# USB_HUB.net
KiCad netlist of a schematic drawn in Altium Designer
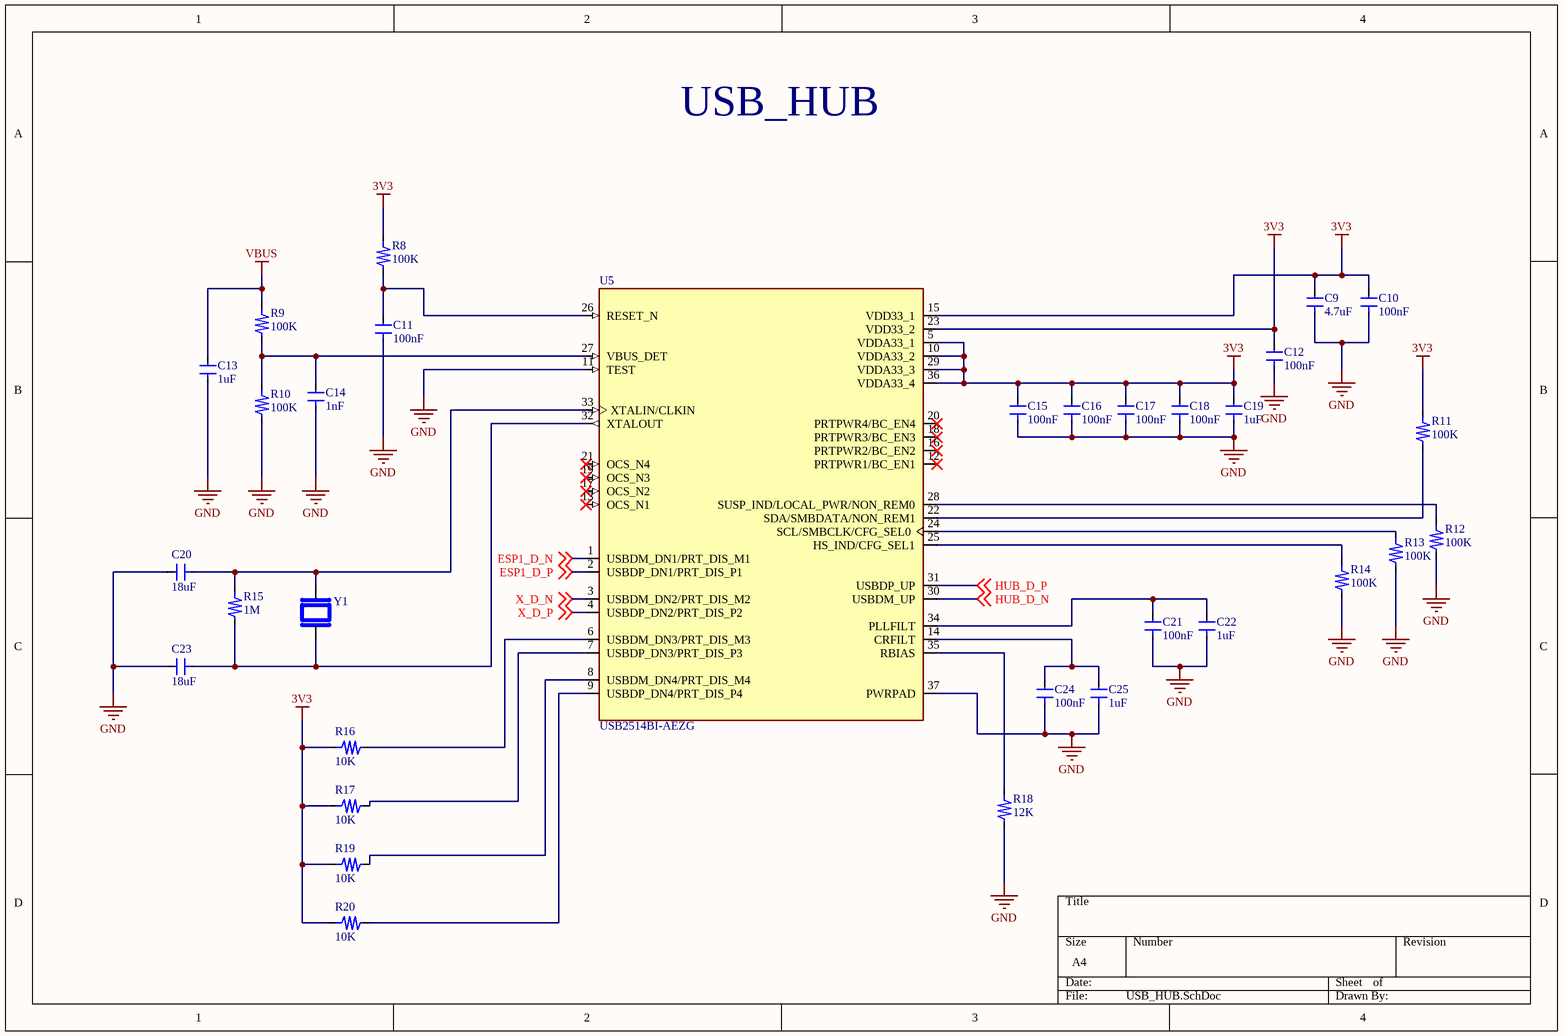
[diagram p0: USB_HUB.SchDoc]

(export (version "E")
  (design (tool "Eeschema 10.0.6"))
  (components
    (comp (ref "C9")
      (value "4.7uF")
      (footprint "CAP 0603")
      (fields (field (name "PART NUMBER") "CL10A475KL8NRNC"))
      (libsource (lib "Schlib2") (part "Capasitor"))
    )
    (comp (ref "C10")
      (value "100nF")
      (footprint "CAP 0603")
      (fields (field (name "PART NUMBER") "CC0603JRX7R9BB104"))
      (libsource (lib "Schlib2") (part "Capasitor"))
    )
    (comp (ref "C11")
      (value "100nF")
      (footprint "CAP 0603")
      (fields (field (name "PART NUMBER") "CC0603JRX7R9BB104"))
      (libsource (lib "Schlib2") (part "Capasitor"))
    )
    (comp (ref "C12")
      (value "100nF")
      (footprint "CAP 0603")
      (fields (field (name "PART NUMBER") "CC0603JRX7R9BB104"))
      (libsource (lib "Schlib2") (part "Capasitor"))
    )
    (comp (ref "C13")
      (value "1uF")
      (footprint "CAP 0603")
      (fields (field (name "PART NUMBER") "CC0603JRX7R7BB105"))
      (libsource (lib "Schlib2") (part "Capasitor"))
    )
    (comp (ref "C14")
      (value "1nF")
      (footprint "CAP 0603")
      (fields (field (name "PART NUMBER") "GRM1885C1H102JA01D"))
      (libsource (lib "Schlib2") (part "Capasitor"))
    )
    (comp (ref "C15")
      (value "100nF")
      (footprint "CAP 0603")
      (fields (field (name "PART NUMBER") "CC0603JRX7R9BB104"))
      (libsource (lib "Schlib2") (part "Capasitor"))
    )
    (comp (ref "C16")
      (value "100nF")
      (footprint "CAP 0603")
      (fields (field (name "PART NUMBER") "CC0603JRX7R9BB104"))
      (libsource (lib "Schlib2") (part "Capasitor"))
    )
    (comp (ref "C17")
      (value "100nF")
      (footprint "CAP 0603")
      (fields (field (name "PART NUMBER") "CC0603JRX7R9BB104"))
      (libsource (lib "Schlib2") (part "Capasitor"))
    )
    (comp (ref "C18")
      (value "100nF")
      (footprint "CAP 0603")
      (fields (field (name "PART NUMBER") "CC0603JRX7R9BB104"))
      (libsource (lib "Schlib2") (part "Capasitor"))
    )
    (comp (ref "C19")
      (value "1uF")
      (footprint "CAP 0603")
      (fields (field (name "PART NUMBER") "CC0603JRX7R7BB105"))
      (libsource (lib "Schlib2") (part "Capasitor"))
    )
    (comp (ref "C20")
      (value "18uF")
      (footprint "CAP 0603")
      (fields (field (name "PART NUMBER") "CC0603FRNPO9BN180"))
      (libsource (lib "Schlib2") (part "Capasitor"))
    )
    (comp (ref "C21")
      (value "100nF")
      (footprint "CAP 0603")
      (fields (field (name "PART NUMBER") "CC0603JRX7R9BB104"))
      (libsource (lib "Schlib2") (part "Capasitor"))
    )
    (comp (ref "C22")
      (value "1uF")
      (footprint "CAP 0603")
      (fields (field (name "PART NUMBER") "CC0603JRX7R7BB105"))
      (libsource (lib "Schlib2") (part "Capasitor"))
    )
    (comp (ref "C23")
      (value "18uF")
      (footprint "CAP 0603")
      (fields (field (name "PART NUMBER") "CC0603FRNPO9BN180"))
      (libsource (lib "Schlib2") (part "Capasitor"))
    )
    (comp (ref "C24")
      (value "100nF")
      (footprint "CAP 0603")
      (fields (field (name "PART NUMBER") "CC0603JRX7R9BB104"))
      (libsource (lib "Schlib2") (part "Capasitor"))
    )
    (comp (ref "C25")
      (value "1uF")
      (footprint "CAP 0603")
      (fields (field (name "PART NUMBER") "CC0603JRX7R7BB105"))
      (libsource (lib "Schlib2") (part "Capasitor"))
    )
    (comp (ref "R8")
      (value "100K")
      (footprint "RES 0603")
      (fields (field (name "PART NUMBER") "RS-03K104JT"))
      (libsource (lib "Schlib2") (part "Resistor"))
    )
    (comp (ref "R9")
      (value "100K")
      (footprint "RES 0603")
      (fields (field (name "PART NUMBER") "RS-03K104JT"))
      (libsource (lib "Schlib2") (part "Resistor"))
    )
    (comp (ref "R10")
      (value "100K")
      (footprint "RES 0603")
      (fields (field (name "PART NUMBER") "RS-03K104JT"))
      (libsource (lib "Schlib2") (part "Resistor"))
    )
    (comp (ref "R11")
      (value "100K")
      (footprint "RES 0603")
      (fields (field (name "PART NUMBER") "RS-03K104JT"))
      (libsource (lib "Schlib2") (part "Resistor"))
    )
    (comp (ref "R12")
      (value "100K")
      (footprint "RES 0603")
      (fields (field (name "PART NUMBER") "RS-03K104JT"))
      (libsource (lib "Schlib2") (part "Resistor"))
    )
    (comp (ref "R13")
      (value "100K")
      (footprint "RES 0603")
      (fields (field (name "PART NUMBER") "RS-03K104JT"))
      (libsource (lib "Schlib2") (part "Resistor"))
    )
    (comp (ref "R14")
      (value "100K")
      (footprint "RES 0603")
      (fields (field (name "PART NUMBER") "RS-03K104JT"))
      (libsource (lib "Schlib2") (part "Resistor"))
    )
    (comp (ref "R15")
      (value "1M")
      (footprint "RES 0603")
      (fields (field (name "PART NUMBER") "RS-03K1004FT"))
      (libsource (lib "Schlib2") (part "Resistor"))
    )
    (comp (ref "R16")
      (value "10K")
      (footprint "RES 0603")
      (fields (field (name "PART NUMBER") "RS-03K1002FT"))
      (libsource (lib "Schlib2") (part "Resistor"))
    )
    (comp (ref "R17")
      (value "10K")
      (footprint "RES 0603")
      (fields (field (name "PART NUMBER") "RS-03K1002FT"))
      (libsource (lib "Schlib2") (part "Resistor"))
    )
    (comp (ref "R18")
      (value "12K")
      (footprint "RES 0603")
      (fields (field (name "PART NUMBER") "RS-03K1202FT"))
      (libsource (lib "Schlib2") (part "Resistor"))
    )
    (comp (ref "R19")
      (value "10K")
      (footprint "RES 0603")
      (fields (field (name "PART NUMBER") "RS-03K1002FT"))
      (libsource (lib "Schlib2") (part "Resistor"))
    )
    (comp (ref "R20")
      (value "10K")
      (footprint "RES 0603")
      (fields (field (name "PART NUMBER") "RS-03K1002FT"))
      (libsource (lib "Schlib2") (part "Resistor"))
    )
    (comp (ref "U5")
      (value "USB2514BI-AEZG")
      (footprint "QFN50P600X600X100-37N")
      (description "USB Hub Controller USB 2.0 USB Interface 36-QFN (6x6)")
      (fields (field (name "PART NUMBER") "USB2514BI-AEZG-TR"))
      (libsource (lib "Schlib2") (part "USB2514BI-AEZG"))
    )
    (comp (ref "Y1")
      (value "ABLS-24.000MHZ-B4-T")
      (footprint "XTAL_ABLS-24.000MHZ-B4-T")
      (description "HC/49US (AT49) SMD LOW PROFILE CRYSTAL")
      (libsource (lib "Schlib2") (part "ABLS-24.000MHZ-B4-T"))
    )
  )
  (nets
    (net (code "1") (name "3V3") (class "Default")
      (node (ref "C10") (pin "2") (pinfunction "2_2") (pintype "passive"))
      (node (ref "C12") (pin "2") (pinfunction "2_2") (pintype "passive"))
      (node (ref "C15") (pin "2") (pinfunction "2_2") (pintype "passive"))
      (node (ref "C16") (pin "2") (pinfunction "2_2") (pintype "passive"))
      (node (ref "C17") (pin "2") (pinfunction "2_2") (pintype "passive"))
      (node (ref "C18") (pin "2") (pinfunction "2_2") (pintype "passive"))
      (node (ref "C19") (pin "2") (pinfunction "2_2") (pintype "passive"))
      (node (ref "C9") (pin "2") (pinfunction "2_2") (pintype "passive"))
      (node (ref "R11") (pin "1") (pinfunction "1_1") (pintype "passive"))
      (node (ref "R16") (pin "1") (pinfunction "1_1") (pintype "passive"))
      (node (ref "R17") (pin "1") (pinfunction "1_1") (pintype "passive"))
      (node (ref "R19") (pin "1") (pinfunction "1_1") (pintype "passive"))
      (node (ref "R20") (pin "1") (pinfunction "1_1") (pintype "passive"))
      (node (ref "R8") (pin "1") (pinfunction "1_1") (pintype "passive"))
      (node (ref "U5") (pin "10") (pinfunction "VDDA33_2_10") (pintype "power_in"))
      (node (ref "U5") (pin "15") (pinfunction "VDD33_1_15") (pintype "passive"))
      (node (ref "U5") (pin "23") (pinfunction "VDD33_2_23") (pintype "passive"))
      (node (ref "U5") (pin "29") (pinfunction "VDDA33_3_29") (pintype "power_in"))
      (node (ref "U5") (pin "36") (pinfunction "VDDA33_4_36") (pintype "power_in"))
      (node (ref "U5") (pin "5") (pinfunction "VDDA33_1_5") (pintype "power_in"))
    )
    (net (code "2") (name "ESP1_D_N") (class "Default")
      (node (ref "U5") (pin "1") (pinfunction "USBDM_DN1/PRT_DIS_M1_1") (pintype "bidirectional"))
    )
    (net (code "3") (name "ESP1_D_P") (class "Default")
      (node (ref "U5") (pin "2") (pinfunction "USBDP_DN1/PRT_DIS_P1_2") (pintype "bidirectional"))
    )
    (net (code "4") (name "GND") (class "Default")
      (node (ref "C10") (pin "1") (pinfunction "1_1") (pintype "passive"))
      (node (ref "C11") (pin "1") (pinfunction "1_1") (pintype "passive"))
      (node (ref "C12") (pin "1") (pinfunction "1_1") (pintype "passive"))
      (node (ref "C13") (pin "1") (pinfunction "1_1") (pintype "passive"))
      (node (ref "C14") (pin "1") (pinfunction "1_1") (pintype "passive"))
      (node (ref "C15") (pin "1") (pinfunction "1_1") (pintype "passive"))
      (node (ref "C16") (pin "1") (pinfunction "1_1") (pintype "passive"))
      (node (ref "C17") (pin "1") (pinfunction "1_1") (pintype "passive"))
      (node (ref "C18") (pin "1") (pinfunction "1_1") (pintype "passive"))
      (node (ref "C19") (pin "1") (pinfunction "1_1") (pintype "passive"))
      (node (ref "C20") (pin "2") (pinfunction "2_2") (pintype "passive"))
      (node (ref "C21") (pin "1") (pinfunction "1_1") (pintype "passive"))
      (node (ref "C22") (pin "1") (pinfunction "1_1") (pintype "passive"))
      (node (ref "C23") (pin "2") (pinfunction "2_2") (pintype "passive"))
      (node (ref "C24") (pin "1") (pinfunction "1_1") (pintype "passive"))
      (node (ref "C25") (pin "1") (pinfunction "1_1") (pintype "passive"))
      (node (ref "C9") (pin "1") (pinfunction "1_1") (pintype "passive"))
      (node (ref "R10") (pin "2") (pinfunction "2_2") (pintype "passive"))
      (node (ref "R12") (pin "2") (pinfunction "2_2") (pintype "passive"))
      (node (ref "R13") (pin "2") (pinfunction "2_2") (pintype "passive"))
      (node (ref "R14") (pin "2") (pinfunction "2_2") (pintype "passive"))
      (node (ref "R18") (pin "2") (pinfunction "2_2") (pintype "passive"))
      (node (ref "U5") (pin "11") (pinfunction "TEST_11") (pintype "input"))
      (node (ref "U5") (pin "37") (pinfunction "PWRPAD_37") (pintype "power_in"))
    )
    (net (code "5") (name "HUB_D_N") (class "Default")
      (node (ref "U5") (pin "30") (pinfunction "USBDM_UP_30") (pintype "bidirectional"))
    )
    (net (code "6") (name "HUB_D_P") (class "Default")
      (node (ref "U5") (pin "31") (pinfunction "USBDP_UP_31") (pintype "bidirectional"))
    )
    (net (code "7") (name "Net-(U5-CRFILT)") (class "Default")
      (node (ref "C24") (pin "2") (pinfunction "2_2") (pintype "passive"))
      (node (ref "C25") (pin "2") (pinfunction "2_2") (pintype "passive"))
      (node (ref "U5") (pin "14") (pinfunction "CRFILT_14") (pintype "passive"))
    )
    (net (code "8") (name "Net-(U5-HS_IND{slash}CFG_SEL1)") (class "Default")
      (node (ref "R14") (pin "1") (pinfunction "1_1") (pintype "passive"))
      (node (ref "U5") (pin "25") (pinfunction "HS_IND/CFG_SEL1_25") (pintype "bidirectional"))
    )
    (net (code "9") (name "Net-(U5-PLLFILT)") (class "Default")
      (node (ref "C21") (pin "2") (pinfunction "2_2") (pintype "passive"))
      (node (ref "C22") (pin "2") (pinfunction "2_2") (pintype "passive"))
      (node (ref "U5") (pin "34") (pinfunction "PLLFILT_34") (pintype "passive"))
    )
    (net (code "10") (name "Net-(U5-RBIAS)") (class "Default")
      (node (ref "R18") (pin "1") (pinfunction "1_1") (pintype "passive"))
      (node (ref "U5") (pin "35") (pinfunction "RBIAS_35") (pintype "passive"))
    )
    (net (code "11") (name "Net-(U5-RESET_N)") (class "Default")
      (node (ref "C11") (pin "2") (pinfunction "2_2") (pintype "passive"))
      (node (ref "R8") (pin "2") (pinfunction "2_2") (pintype "passive"))
      (node (ref "U5") (pin "26") (pinfunction "RESET_N_26") (pintype "input"))
    )
    (net (code "12") (name "Net-(U5-SCL{slash}SMBCLK{slash}CFG_SEL0)") (class "Default")
      (node (ref "R13") (pin "1") (pinfunction "1_1") (pintype "passive"))
      (node (ref "U5") (pin "24") (pinfunction "SCL/SMBCLK/CFG_SEL0_24") (pintype "bidirectional"))
    )
    (net (code "13") (name "Net-(U5-SDA{slash}SMBDATA{slash}NON_REM1)") (class "Default")
      (node (ref "R11") (pin "2") (pinfunction "2_2") (pintype "passive"))
      (node (ref "U5") (pin "22") (pinfunction "SDA/SMBDATA/NON_REM1_22") (pintype "bidirectional"))
    )
    (net (code "14") (name "Net-(U5-SUSP_IND{slash}LOCAL_PWR{slash}NON_REM0)") (class "Default")
      (node (ref "R12") (pin "1") (pinfunction "1_1") (pintype "passive"))
      (node (ref "U5") (pin "28") (pinfunction "SUSP_IND/LOCAL_PWR/NON_REM0_28") (pintype "bidirectional"))
    )
    (net (code "15") (name "Net-(U5-USBDM_DN3{slash}PRT_DIS_M3)") (class "Default")
      (node (ref "R16") (pin "2") (pinfunction "2_2") (pintype "passive"))
      (node (ref "U5") (pin "6") (pinfunction "USBDM_DN3/PRT_DIS_M3_6") (pintype "bidirectional"))
    )
    (net (code "16") (name "Net-(U5-USBDM_DN4{slash}PRT_DIS_M4)") (class "Default")
      (node (ref "R19") (pin "2") (pinfunction "2_2") (pintype "passive"))
      (node (ref "U5") (pin "8") (pinfunction "USBDM_DN4/PRT_DIS_M4_8") (pintype "bidirectional"))
    )
    (net (code "17") (name "Net-(U5-USBDP_DN3{slash}PRT_DIS_P3)") (class "Default")
      (node (ref "R17") (pin "2") (pinfunction "2_2") (pintype "passive"))
      (node (ref "U5") (pin "7") (pinfunction "USBDP_DN3/PRT_DIS_P3_7") (pintype "bidirectional"))
    )
    (net (code "18") (name "Net-(U5-USBDP_DN4{slash}PRT_DIS_P4)") (class "Default")
      (node (ref "R20") (pin "2") (pinfunction "2_2") (pintype "passive"))
      (node (ref "U5") (pin "9") (pinfunction "USBDP_DN4/PRT_DIS_P4_9") (pintype "bidirectional"))
    )
    (net (code "19") (name "Net-(U5-VBUS_DET)") (class "Default")
      (node (ref "C14") (pin "2") (pinfunction "2_2") (pintype "passive"))
      (node (ref "R10") (pin "1") (pinfunction "1_1") (pintype "passive"))
      (node (ref "R9") (pin "2") (pinfunction "2_2") (pintype "passive"))
      (node (ref "U5") (pin "27") (pinfunction "VBUS_DET_27") (pintype "input"))
    )
    (net (code "20") (name "Net-(U5-XTALIN{slash}CLKIN)") (class "Default")
      (node (ref "C20") (pin "1") (pinfunction "1_1") (pintype "passive"))
      (node (ref "R15") (pin "1") (pinfunction "1_1") (pintype "passive"))
      (node (ref "U5") (pin "33") (pinfunction "XTALIN/CLKIN_33") (pintype "input"))
      (node (ref "Y1") (pin "2") (pinfunction "2_2") (pintype "passive"))
    )
    (net (code "21") (name "Net-(U5-XTALOUT)") (class "Default")
      (node (ref "C23") (pin "1") (pinfunction "1_1") (pintype "passive"))
      (node (ref "R15") (pin "2") (pinfunction "2_2") (pintype "passive"))
      (node (ref "U5") (pin "32") (pinfunction "XTALOUT_32") (pintype "output"))
      (node (ref "Y1") (pin "1") (pinfunction "1_1") (pintype "passive"))
    )
    (net (code "22") (name "VBUS") (class "Default")
      (node (ref "C13") (pin "2") (pinfunction "2_2") (pintype "passive"))
      (node (ref "R9") (pin "1") (pinfunction "1_1") (pintype "passive"))
    )
    (net (code "23") (name "X_D_N") (class "Default")
      (node (ref "U5") (pin "3") (pinfunction "USBDM_DN2/PRT_DIS_M2_3") (pintype "bidirectional"))
    )
    (net (code "24") (name "X_D_P") (class "Default")
      (node (ref "U5") (pin "4") (pinfunction "USBDP_DN2/PRT_DIS_P2_4") (pintype "bidirectional"))
    )
    (net (code "25") (name "unconnected-(U5-OCS_N1-Pad13)") (class "Default")
      (node (ref "U5") (pin "13") (pinfunction "OCS_N1_13") (pintype "input+no_connect"))
    )
    (net (code "26") (name "unconnected-(U5-OCS_N2-Pad17)") (class "Default")
      (node (ref "U5") (pin "17") (pinfunction "OCS_N2_17") (pintype "input+no_connect"))
    )
    (net (code "27") (name "unconnected-(U5-OCS_N3-Pad19)") (class "Default")
      (node (ref "U5") (pin "19") (pinfunction "OCS_N3_19") (pintype "input+no_connect"))
    )
    (net (code "28") (name "unconnected-(U5-OCS_N4-Pad21)") (class "Default")
      (node (ref "U5") (pin "21") (pinfunction "OCS_N4_21") (pintype "input+no_connect"))
    )
    (net (code "29") (name "unconnected-(U5-PRTPWR1{slash}BC_EN1-Pad12)") (class "Default")
      (node (ref "U5") (pin "12") (pinfunction "PRTPWR1/BC_EN1_12") (pintype "bidirectional+no_connect"))
    )
    (net (code "30") (name "unconnected-(U5-PRTPWR2{slash}BC_EN2-Pad16)") (class "Default")
      (node (ref "U5") (pin "16") (pinfunction "PRTPWR2/BC_EN2_16") (pintype "bidirectional+no_connect"))
    )
    (net (code "31") (name "unconnected-(U5-PRTPWR3{slash}BC_EN3-Pad18)") (class "Default")
      (node (ref "U5") (pin "18") (pinfunction "PRTPWR3/BC_EN3_18") (pintype "bidirectional+no_connect"))
    )
    (net (code "32") (name "unconnected-(U5-PRTPWR4{slash}BC_EN4-Pad20)") (class "Default")
      (node (ref "U5") (pin "20") (pinfunction "PRTPWR4/BC_EN4_20") (pintype "bidirectional+no_connect"))
    )
  )
)
